# esp8266_3C_noGND.net
KiCad netlist of a schematic drawn in EAGLE
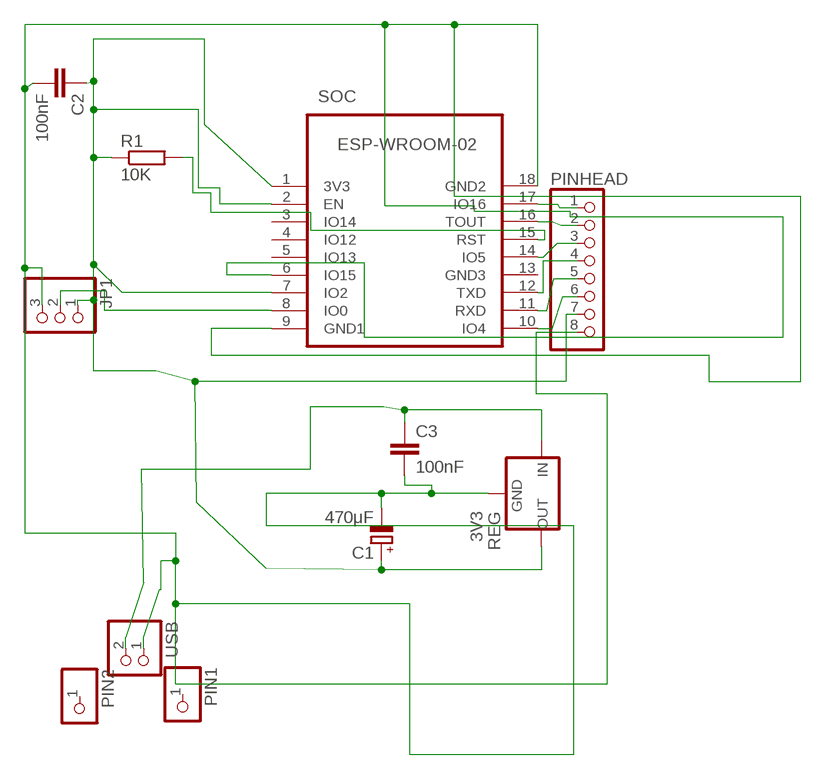
[diagram p0: schematic, sheet 1]

(export (version "E")
  (design (tool "Eeschema 10.0.6"))
  (components
    (comp (ref "C1")
      (value "470μF")
      (footprint "eagle-import:E2,5-7")
      (libsource (lib "eagle-import") (part "CPOL-EUE2.5-7"))
    )
    (comp (ref "C2")
      (value "100nF")
      (footprint "eagle-import:C0603")
      (libsource (lib "eagle-import") (part "C-EUC0603"))
    )
    (comp (ref "C3")
      (value "100nF")
      (footprint "eagle-import:C0603")
      (libsource (lib "eagle-import") (part "C-EUC0603"))
    )
    (comp (ref "JP1")
      (value "PINHD-1X3")
      (footprint "eagle-import:1X03")
      (libsource (lib "eagle-import") (part "PINHD-1X3"))
    )
    (comp (ref "PIN1")
      (value "PINHD-1X1")
      (footprint "eagle-import:1X01")
      (libsource (lib "eagle-import") (part "PINHD-1X1"))
    )
    (comp (ref "PIN2")
      (value "PINHD-1X1")
      (footprint "eagle-import:1X01")
      (libsource (lib "eagle-import") (part "PINHD-1X1"))
    )
    (comp (ref "PINHEAD")
      (value "PINHD-1X8")
      (footprint "eagle-import:1X08")
      (libsource (lib "eagle-import") (part "PINHD-1X8"))
    )
    (comp (ref "R1")
      (value "10K")
      (footprint "eagle-import:R0603")
      (libsource (lib "eagle-import") (part "R-EU_R0603"))
    )
    (comp (ref "REG")
      (value "3V3")
      (footprint "eagle-import:78XXS")
      (libsource (lib "eagle-import") (part "78XXS"))
    )
    (comp (ref "SOC")
      (value "ESP-WROOM-02")
      (footprint "eagle-import:FRONT-FACE-CP2")
      (libsource (lib "eagle-import") (part "ESP-WROOM-02-CP2FRONT"))
    )
    (comp (ref "USB")
      (value "PINHD-1X2")
      (footprint "eagle-import:1X02")
      (libsource (lib "eagle-import") (part "PINHD-1X2"))
    )
  )
  (nets
    (net (code "1") (name "Net-(C3-Pad1)") (class "Default")
      (node (ref "C3") (pin "1") (pinfunction "1_1") (pintype "passive"))
      (node (ref "REG") (pin "IN") (pinfunction "IN_IN") (pintype "input"))
      (node (ref "USB") (pin "2") (pinfunction "2_2") (pintype "passive"))
    )
    (net (code "2") (name "Net-(SOC-3V3)") (class "Default")
      (node (ref "C1") (pin "+") (pinfunction "+_+") (pintype "passive"))
      (node (ref "C2") (pin "1") (pinfunction "1_1") (pintype "passive"))
      (node (ref "JP1") (pin "1") (pinfunction "1_1") (pintype "passive"))
      (node (ref "PINHEAD") (pin "7") (pinfunction "7_7") (pintype "passive"))
      (node (ref "R1") (pin "1") (pinfunction "1_1") (pintype "passive"))
      (node (ref "REG") (pin "OUT") (pinfunction "OUT_OUT") (pintype "passive"))
      (node (ref "SOC") (pin "1") (pinfunction "3V3_1") (pintype "bidirectional"))
      (node (ref "SOC") (pin "2") (pinfunction "EN_2") (pintype "bidirectional"))
      (node (ref "SOC") (pin "7") (pinfunction "IO2_7") (pintype "bidirectional"))
    )
    (net (code "3") (name "Net-(SOC-GND1)") (class "Default")
      (node (ref "C1") (pin "-") (pinfunction "-_-") (pintype "passive"))
      (node (ref "C2") (pin "2") (pinfunction "2_2") (pintype "passive"))
      (node (ref "C3") (pin "2") (pinfunction "2_2") (pintype "passive"))
      (node (ref "JP1") (pin "3") (pinfunction "3_3") (pintype "passive"))
      (node (ref "PINHEAD") (pin "8") (pinfunction "8_8") (pintype "passive"))
      (node (ref "REG") (pin "GND") (pinfunction "GND_GND") (pintype "input"))
      (node (ref "SOC") (pin "18") (pinfunction "GND2_18") (pintype "bidirectional"))
      (node (ref "SOC") (pin "6") (pinfunction "IO15_6") (pintype "bidirectional"))
      (node (ref "SOC") (pin "9") (pinfunction "GND1_9") (pintype "bidirectional"))
      (node (ref "USB") (pin "1") (pinfunction "1_1") (pintype "passive"))
    )
    (net (code "4") (name "Net-(SOC-IO0)") (class "Default")
      (node (ref "JP1") (pin "2") (pinfunction "2_2") (pintype "passive"))
      (node (ref "SOC") (pin "8") (pinfunction "IO0_8") (pintype "bidirectional"))
    )
    (net (code "5") (name "Net-(SOC-IO4)") (class "Default")
      (node (ref "PINHEAD") (pin "6") (pinfunction "6_6") (pintype "passive"))
      (node (ref "SOC") (pin "10") (pinfunction "IO4_10") (pintype "bidirectional"))
    )
    (net (code "6") (name "Net-(SOC-IO5)") (class "Default")
      (node (ref "PINHEAD") (pin "3") (pinfunction "3_3") (pintype "passive"))
      (node (ref "SOC") (pin "14") (pinfunction "IO5_14") (pintype "bidirectional"))
    )
    (net (code "7") (name "Net-(SOC-IO16)") (class "Default")
      (node (ref "PINHEAD") (pin "1") (pinfunction "1_1") (pintype "passive"))
      (node (ref "SOC") (pin "17") (pinfunction "IO16_17") (pintype "bidirectional"))
    )
    (net (code "8") (name "Net-(SOC-RST)") (class "Default")
      (node (ref "R1") (pin "2") (pinfunction "2_2") (pintype "passive"))
      (node (ref "SOC") (pin "15") (pinfunction "RST_15") (pintype "bidirectional"))
    )
    (net (code "9") (name "Net-(SOC-RXD)") (class "Default")
      (node (ref "PINHEAD") (pin "5") (pinfunction "5_5") (pintype "passive"))
      (node (ref "SOC") (pin "11") (pinfunction "RXD_11") (pintype "bidirectional"))
    )
    (net (code "10") (name "Net-(SOC-TOUT)") (class "Default")
      (node (ref "PINHEAD") (pin "2") (pinfunction "2_2") (pintype "passive"))
      (node (ref "SOC") (pin "16") (pinfunction "TOUT_16") (pintype "bidirectional"))
    )
    (net (code "11") (name "Net-(SOC-TXD)") (class "Default")
      (node (ref "PINHEAD") (pin "4") (pinfunction "4_4") (pintype "passive"))
      (node (ref "SOC") (pin "12") (pinfunction "TXD_12") (pintype "bidirectional"))
    )
    (net (code "12") (name "unconnected-(PIN1-Pad1)") (class "Default")
      (node (ref "PIN1") (pin "1") (pinfunction "1_1") (pintype "passive"))
    )
    (net (code "13") (name "unconnected-(PIN2-Pad1)") (class "Default")
      (node (ref "PIN2") (pin "1") (pinfunction "1_1") (pintype "passive"))
    )
    (net (code "14") (name "unconnected-(SOC-GND3-Pad13)") (class "Default")
      (node (ref "SOC") (pin "13") (pinfunction "GND3_13") (pintype "bidirectional"))
    )
    (net (code "15") (name "unconnected-(SOC-IO12-Pad4)") (class "Default")
      (node (ref "SOC") (pin "4") (pinfunction "IO12_4") (pintype "bidirectional"))
    )
    (net (code "16") (name "unconnected-(SOC-IO13-Pad5)") (class "Default")
      (node (ref "SOC") (pin "5") (pinfunction "IO13_5") (pintype "open_collector"))
    )
    (net (code "17") (name "unconnected-(SOC-IO14-Pad3)") (class "Default")
      (node (ref "SOC") (pin "3") (pinfunction "IO14_3") (pintype "bidirectional"))
    )
  )
)
